# connectors.net
KiCad netlist of a schematic drawn in EAGLE
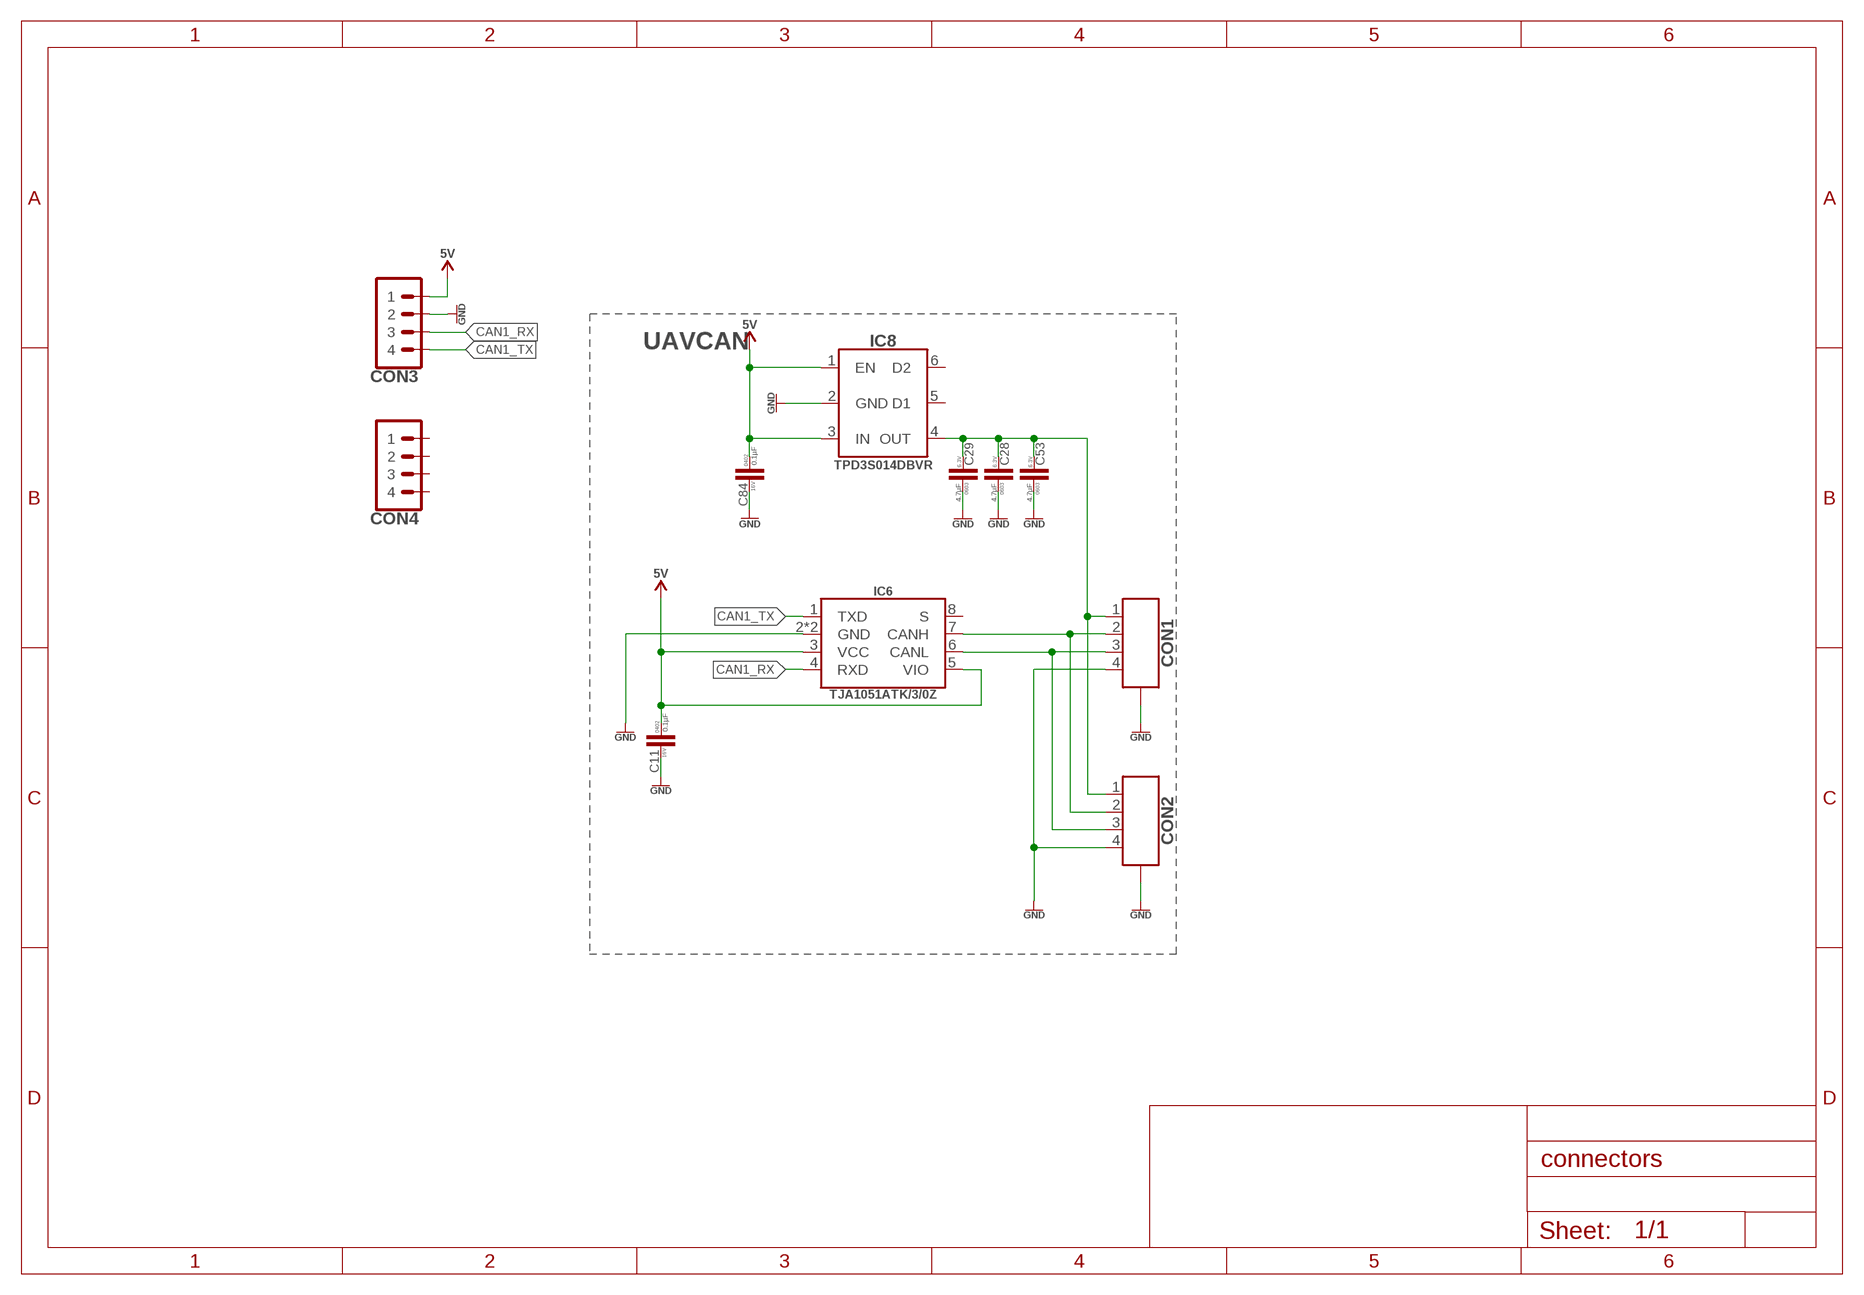
[diagram p0: schematic, sheet 1]

(export (version "E")
  (design (tool "Eeschema 10.0.6"))
  (components
    (comp (ref "C11")
      (value "0.1µF")
      (footprint "eagle-import:C0402")
      (fields
        (field (name "PACKAGE") "0402")
        (field (name "AEC-Q") "---")
        (field (name "DIGIKEY#") "490-3261-1-ND")
        (field (name "MANF") "Murata Electronics")
        (field (name "MANF#") "GRM155R71C104KA88D")
        (field (name "OPERATING_TEMP") "-55°C ~ 125°C")
        (field (name "VOLTAGE") "16V")
      )
      (libsource (lib "eagle-import") (part "C-0402"))
    )
    (comp (ref "C28")
      (value "4.7µF")
      (footprint "eagle-import:C0603")
      (fields
        (field (name "PACKAGE") "0603")
        (field (name "AEC-Q") "---")
        (field (name "DIGIKEY#") "1276-2087-1-ND")
        (field (name "MANF") "Samsung Electro-Mechanics")
        (field (name "MANF#") "CL10B475KQ8NQNC")
        (field (name "OPERATING_TEMP") "-55°C ~ 125°C")
        (field (name "VOLTAGE") "6.3V")
      )
      (libsource (lib "eagle-import") (part "C-0603"))
    )
    (comp (ref "C29")
      (value "4.7µF")
      (footprint "eagle-import:C0603")
      (fields
        (field (name "PACKAGE") "0603")
        (field (name "AEC-Q") "---")
        (field (name "DIGIKEY#") "1276-2087-1-ND")
        (field (name "MANF") "Samsung Electro-Mechanics")
        (field (name "MANF#") "CL10B475KQ8NQNC")
        (field (name "OPERATING_TEMP") "-55°C ~ 125°C")
        (field (name "VOLTAGE") "6.3V")
      )
      (libsource (lib "eagle-import") (part "C-0603"))
    )
    (comp (ref "C53")
      (value "4.7µF")
      (footprint "eagle-import:C0603")
      (fields
        (field (name "PACKAGE") "0603")
        (field (name "AEC-Q") "---")
        (field (name "DIGIKEY#") "1276-2087-1-ND")
        (field (name "MANF") "Samsung Electro-Mechanics")
        (field (name "MANF#") "CL10B475KQ8NQNC")
        (field (name "OPERATING_TEMP") "-55°C ~ 125°C")
        (field (name "VOLTAGE") "6.3V")
      )
      (libsource (lib "eagle-import") (part "C-0603"))
    )
    (comp (ref "C84")
      (value "0.1µF")
      (footprint "eagle-import:C0402")
      (fields
        (field (name "PACKAGE") "0402")
        (field (name "AEC-Q") "---")
        (field (name "DIGIKEY#") "490-3261-1-ND")
        (field (name "MANF") "Murata Electronics")
        (field (name "MANF#") "GRM155R71C104KA88D")
        (field (name "OPERATING_TEMP") "-55°C ~ 125°C")
        (field (name "VOLTAGE") "16V")
      )
      (libsource (lib "eagle-import") (part "C-0402"))
    )
    (comp (ref "CON1")
      (value "CON-4P-TABS-JST_GH-RA")
      (footprint "eagle-import:JST_GH-4P-RA")
      (fields (field (name "MANF") "JST Sales America Inc"))
      (libsource (lib "eagle-import") (part "CON-4P-TABS-RA-JST_GH"))
    )
    (comp (ref "CON2")
      (value "CON-4P-TABS-JST_GH-RA")
      (footprint "eagle-import:JST_GH-4P-RA")
      (fields (field (name "MANF") "JST Sales America Inc"))
      (libsource (lib "eagle-import") (part "CON-4P-TABS-RA-JST_GH"))
    )
    (comp (ref "CON3")
      (value "PINHEAD_1X04-2-FEMALE")
      (footprint "eagle-import:1X04-PTH-2-FEMALE")
      (libsource (lib "eagle-import") (part "PINHEAD_1X04-2-FEMALE"))
    )
    (comp (ref "CON4")
      (value "PINHEAD_1X04-2-FEMALE")
      (footprint "eagle-import:1X04-PTH-2-FEMALE")
      (libsource (lib "eagle-import") (part "PINHEAD_1X04-2-FEMALE"))
    )
    (comp (ref "IC6")
      (value "TJA1051-HVSON8")
      (footprint "eagle-import:SOT782-1")
      (fields (field (name "MANF#") "TJA1051ATK/3/0Z") (field (name "MANF") "NXP USA Inc."))
      (libsource (lib "eagle-import") (part "TJA1051-HVSON8"))
    )
    (comp (ref "IC8")
      (value "TPD3S014DBVR-SOT23-6")
      (footprint "eagle-import:SOT26")
      (fields (field (name "MANF#") "TPD3S014DBVR") (field (name "MANF") "Texas Instruments"))
      (libsource (lib "eagle-import") (part "TPD3S014DBVR-SOT23-6"))
    )
  )
  (nets
    (net (code "1") (name "5V") (class "Default")
      (node (ref "C11") (pin "1") (pinfunction "1_1") (pintype "passive"))
      (node (ref "C84") (pin "1") (pinfunction "1_1") (pintype "passive"))
      (node (ref "CON3") (pin "1") (pinfunction "1_1") (pintype "passive"))
      (node (ref "IC6") (pin "3") (pinfunction "VCC_3") (pintype "bidirectional"))
      (node (ref "IC6") (pin "5") (pinfunction "VIO_5") (pintype "bidirectional"))
      (node (ref "IC8") (pin "1") (pinfunction "EN_1") (pintype "bidirectional"))
      (node (ref "IC8") (pin "3") (pinfunction "IN_3") (pintype "bidirectional"))
    )
    (net (code "2") (name "CAN1_RX") (class "Default")
      (node (ref "CON3") (pin "3") (pinfunction "3_3") (pintype "passive"))
      (node (ref "IC6") (pin "4") (pinfunction "RXD_4") (pintype "bidirectional"))
    )
    (net (code "3") (name "CAN1_TX") (class "Default")
      (node (ref "CON3") (pin "4") (pinfunction "4_4") (pintype "passive"))
      (node (ref "IC6") (pin "1") (pinfunction "TXD_1") (pintype "bidirectional"))
    )
    (net (code "4") (name "GND") (class "Default")
      (node (ref "C11") (pin "2") (pinfunction "2_2") (pintype "passive"))
      (node (ref "C28") (pin "1") (pinfunction "1_1") (pintype "passive"))
      (node (ref "C29") (pin "1") (pinfunction "1_1") (pintype "passive"))
      (node (ref "C53") (pin "1") (pinfunction "1_1") (pintype "passive"))
      (node (ref "C84") (pin "2") (pinfunction "2_2") (pintype "passive"))
      (node (ref "CON1") (pin "4") (pinfunction "4_4") (pintype "bidirectional"))
      (node (ref "CON1") (pin "M$0") (pinfunction "GND_M$0") (pintype "bidirectional"))
      (node (ref "CON1") (pin "M$1") (pinfunction "GND_M$1") (pintype "bidirectional"))
      (node (ref "CON2") (pin "4") (pinfunction "4_4") (pintype "bidirectional"))
      (node (ref "CON2") (pin "M$0") (pinfunction "GND_M$0") (pintype "bidirectional"))
      (node (ref "CON2") (pin "M$1") (pinfunction "GND_M$1") (pintype "bidirectional"))
      (node (ref "CON3") (pin "2") (pinfunction "2_2") (pintype "passive"))
      (node (ref "IC6") (pin "2") (pinfunction "GND_2") (pintype "bidirectional"))
      (node (ref "IC6") (pin "PAD") (pinfunction "GND_PAD") (pintype "bidirectional"))
      (node (ref "IC8") (pin "2") (pinfunction "GND_2") (pintype "bidirectional"))
    )
    (net (code "5") (name "Net-(IC6-CANH)") (class "Default")
      (node (ref "CON1") (pin "2") (pinfunction "2_2") (pintype "bidirectional"))
      (node (ref "CON2") (pin "2") (pinfunction "2_2") (pintype "bidirectional"))
      (node (ref "IC6") (pin "7") (pinfunction "CANH_7") (pintype "bidirectional"))
    )
    (net (code "6") (name "Net-(IC6-CANL)") (class "Default")
      (node (ref "CON1") (pin "3") (pinfunction "3_3") (pintype "bidirectional"))
      (node (ref "CON2") (pin "3") (pinfunction "3_3") (pintype "bidirectional"))
      (node (ref "IC6") (pin "6") (pinfunction "CANL_6") (pintype "bidirectional"))
    )
    (net (code "7") (name "Net-(IC8-OUT)") (class "Default")
      (node (ref "C28") (pin "2") (pinfunction "2_2") (pintype "passive"))
      (node (ref "C29") (pin "2") (pinfunction "2_2") (pintype "passive"))
      (node (ref "C53") (pin "2") (pinfunction "2_2") (pintype "passive"))
      (node (ref "CON1") (pin "1") (pinfunction "1_1") (pintype "bidirectional"))
      (node (ref "CON2") (pin "1") (pinfunction "1_1") (pintype "bidirectional"))
      (node (ref "IC8") (pin "4") (pinfunction "OUT_4") (pintype "bidirectional"))
    )
    (net (code "8") (name "unconnected-(CON4-Pad1)") (class "Default")
      (node (ref "CON4") (pin "1") (pinfunction "1_1") (pintype "passive"))
    )
    (net (code "9") (name "unconnected-(CON4-Pad2)") (class "Default")
      (node (ref "CON4") (pin "2") (pinfunction "2_2") (pintype "passive"))
    )
    (net (code "10") (name "unconnected-(CON4-Pad3)") (class "Default")
      (node (ref "CON4") (pin "3") (pinfunction "3_3") (pintype "passive"))
    )
    (net (code "11") (name "unconnected-(CON4-Pad4)") (class "Default")
      (node (ref "CON4") (pin "4") (pinfunction "4_4") (pintype "passive"))
    )
    (net (code "12") (name "unconnected-(IC6-S-Pad8)") (class "Default")
      (node (ref "IC6") (pin "8") (pinfunction "S_8") (pintype "bidirectional"))
    )
    (net (code "13") (name "unconnected-(IC8-D1-Pad5)") (class "Default")
      (node (ref "IC8") (pin "5") (pinfunction "D1_5") (pintype "bidirectional"))
    )
    (net (code "14") (name "unconnected-(IC8-D2-Pad6)") (class "Default")
      (node (ref "IC8") (pin "6") (pinfunction "D2_6") (pintype "bidirectional"))
    )
  )
)
